# USBHeaders.net
KiCad netlist of a schematic drawn in Altium Designer
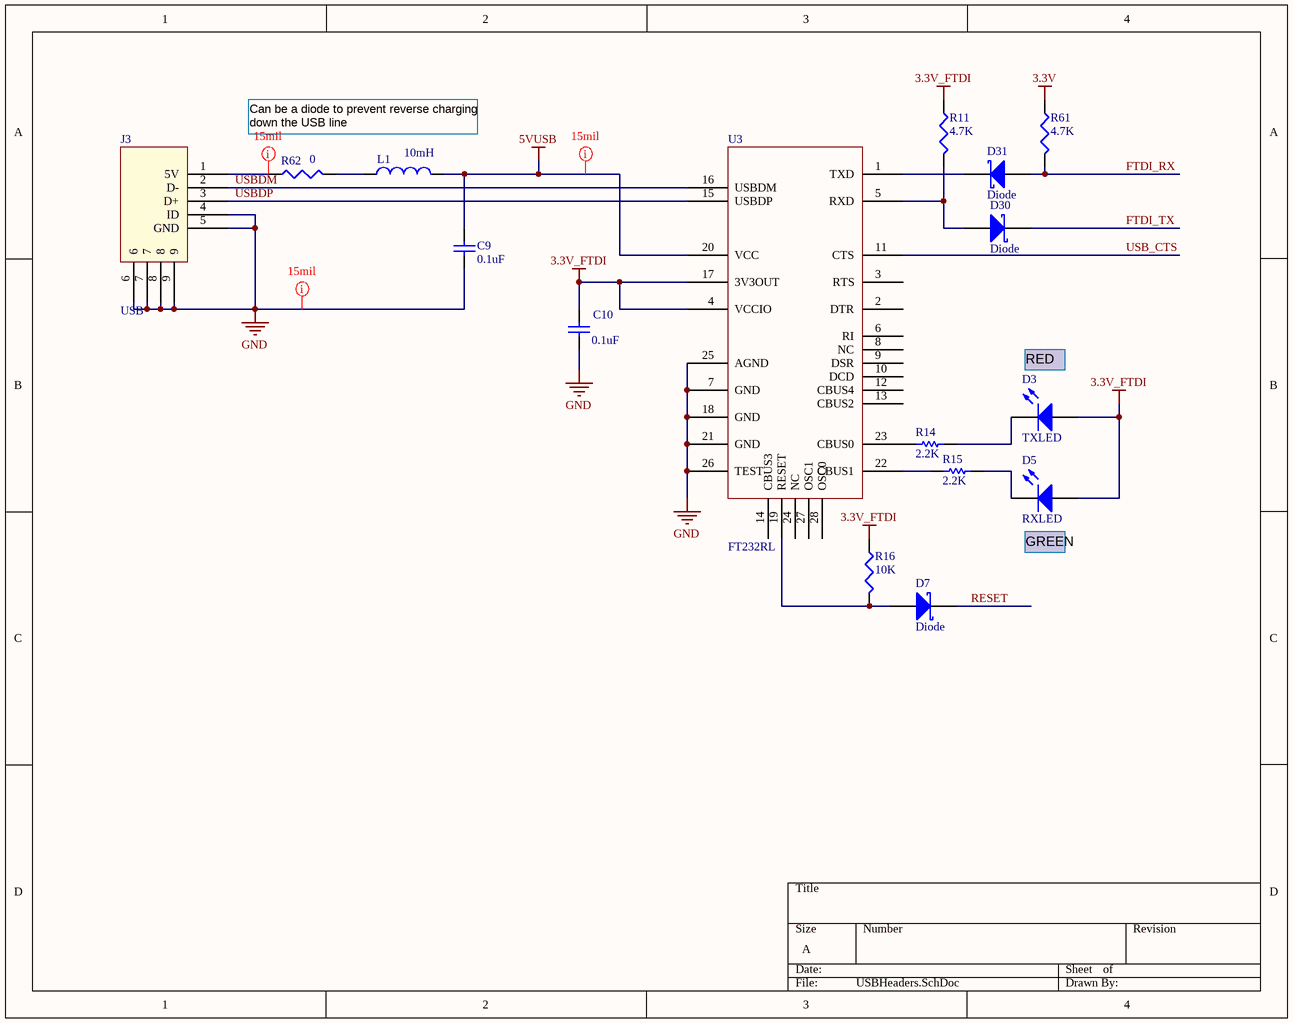
[diagram p0: USBHeaders.SchDoc]

(export (version "E")
  (design (tool "Eeschema 10.0.6"))
  (components
    (comp (ref "C9")
      (value "0.1uF")
      (footprint "CAPC1005L")
      (description "Capacitor")
      (fields (field (name "PUBLISHER") "Altium Limited"))
      (libsource (lib "Miscellaneous Devices") (part "Cap"))
    )
    (comp (ref "C10")
      (value "0.1uF")
      (footprint "CAPC1005L")
      (description "Capacitor")
      (fields (field (name "PUBLISHER") "Altium Limited"))
      (libsource (lib "Miscellaneous Devices") (part "Cap"))
    )
    (comp (ref "D3")
      (value "TXLED")
      (footprint "SurfaceMount(603)")
      (description "Typical RED, GREEN, YELLOW, AMBER GaAs LED")
      (fields (field (name "PUBLISHER") "Altium Limited"))
      (libsource (lib "Miscellaneous Devices") (part "LED2"))
    )
    (comp (ref "D5")
      (value "RXLED")
      (footprint "SurfaceMount(603)")
      (description "Typical RED, GREEN, YELLOW, AMBER GaAs LED")
      (fields (field (name "PUBLISHER") "Altium Limited"))
      (libsource (lib "Miscellaneous Devices") (part "LED2"))
    )
    (comp (ref "D7")
      (value "Diode")
      (footprint "SurfaceMount(603)")
      (libsource (lib "mrone") (part "SchottkeyDiode"))
    )
    (comp (ref "D30")
      (value "Diode")
      (footprint "SurfaceMount(603)")
      (libsource (lib "mrone") (part "SchottkeyDiode"))
    )
    (comp (ref "D31")
      (value "Diode")
      (footprint "SurfaceMount(603)")
      (libsource (lib "mrone") (part "SchottkeyDiode"))
    )
    (comp (ref "J3")
      (value "USB")
      (footprint "USB Minib (thru-hole)")
      (libsource (lib "mrone") (part "USB-ConnTH"))
    )
    (comp (ref "L1")
      (value "10mH")
      (footprint "INDC2012L")
      (description "Inductor")
      (fields (field (name "PUBLISHER") "Altium Limited"))
      (libsource (lib "Miscellaneous Devices") (part "Inductor"))
    )
    (comp (ref "R11")
      (value "4.7K")
      (footprint "RESC1608L")
      (description "Resistor")
      (fields (field (name "Comment") "Res3") (field (name "PUBLISHER") "Altium Limited"))
      (libsource (lib "Miscellaneous Devices") (part "Res3"))
    )
    (comp (ref "R14")
      (value "2.2K")
      (footprint "RESC1608L")
      (description "Resistor")
      (fields (field (name "PUBLISHER") "Altium Limited"))
      (libsource (lib "Miscellaneous Devices") (part "Res1"))
    )
    (comp (ref "R15")
      (value "2.2K")
      (footprint "RESC1608L")
      (description "Resistor")
      (fields (field (name "PUBLISHER") "Altium Limited"))
      (libsource (lib "Miscellaneous Devices") (part "Res1"))
    )
    (comp (ref "R16")
      (value "10K")
      (footprint "RESC1608L")
      (description "Resistor")
      (fields (field (name "Comment") "Res3") (field (name "PUBLISHER") "Altium Limited"))
      (libsource (lib "Miscellaneous Devices") (part "Res3"))
    )
    (comp (ref "R61")
      (value "4.7K")
      (footprint "RESC1608L")
      (description "Resistor")
      (fields (field (name "Comment") "Res3") (field (name "PUBLISHER") "Altium Limited"))
      (libsource (lib "Miscellaneous Devices") (part "Res3"))
    )
    (comp (ref "R62")
      (value "0")
      (footprint "RESC1608L")
      (description "Resistor")
      (fields (field (name "Comment") "Res3") (field (name "PUBLISHER") "Altium Limited"))
      (libsource (lib "Miscellaneous Devices") (part "Res3"))
    )
    (comp (ref "U3") (value "FT232RL") (footprint "SSOP-28") (libsource (lib "mrone") (part "FT232RL")))
  )
  (nets
    (net (code "1") (name "/FTDI_RX") (class "Default")
      (node (ref "D31") (pin "2") (pinfunction "A_2") (pintype "passive"))
      (node (ref "R61") (pin "2") (pinfunction "2_2") (pintype "passive"))
    )
    (net (code "2") (name "/FTDI_TX") (class "Default")
      (node (ref "D30") (pin "1") (pinfunction "K_1") (pintype "passive"))
    )
    (net (code "3") (name "/RESET") (class "Default")
      (node (ref "D7") (pin "1") (pinfunction "K_1") (pintype "passive"))
    )
    (net (code "4") (name "/USBDM") (class "Default")
      (node (ref "J3") (pin "2") (pinfunction "D-_2") (pintype "passive"))
      (node (ref "U3") (pin "16") (pinfunction "USBDM_16") (pintype "passive"))
    )
    (net (code "5") (name "/USBDP") (class "Default")
      (node (ref "J3") (pin "3") (pinfunction "D+_3") (pintype "passive"))
      (node (ref "U3") (pin "15") (pinfunction "USBDP_15") (pintype "passive"))
    )
    (net (code "6") (name "/USB_CTS") (class "Default")
      (node (ref "U3") (pin "11") (pinfunction "CTS_11") (pintype "passive"))
    )
    (net (code "7") (name "3.3V") (class "Default")
      (node (ref "R61") (pin "1") (pinfunction "1_1") (pintype "passive"))
    )
    (net (code "8") (name "3.3V_FTDI") (class "Default")
      (node (ref "C10") (pin "2") (pinfunction "2_2") (pintype "passive"))
      (node (ref "D3") (pin "1") (pinfunction "A_1") (pintype "passive"))
      (node (ref "D5") (pin "1") (pinfunction "A_1") (pintype "passive"))
      (node (ref "R11") (pin "1") (pinfunction "1_1") (pintype "passive"))
      (node (ref "R16") (pin "1") (pinfunction "1_1") (pintype "passive"))
      (node (ref "U3") (pin "17") (pinfunction "3V3OUT_17") (pintype "passive"))
      (node (ref "U3") (pin "4") (pinfunction "VCCIO_4") (pintype "passive"))
    )
    (net (code "9") (name "5VUSB") (class "Default")
      (node (ref "C9") (pin "2") (pinfunction "2_2") (pintype "passive"))
      (node (ref "L1") (pin "2") (pinfunction "2_2") (pintype "passive"))
      (node (ref "U3") (pin "20") (pinfunction "VCC_20") (pintype "passive"))
    )
    (net (code "10") (name "GND") (class "Default")
      (node (ref "C10") (pin "1") (pinfunction "1_1") (pintype "passive"))
      (node (ref "C9") (pin "1") (pinfunction "1_1") (pintype "passive"))
      (node (ref "J3") (pin "4") (pinfunction "ID_4") (pintype "passive"))
      (node (ref "J3") (pin "5") (pinfunction "GND_5") (pintype "passive"))
      (node (ref "J3") (pin "6") (pinfunction "6_6") (pintype "passive"))
      (node (ref "J3") (pin "7") (pinfunction "7_7") (pintype "passive"))
      (node (ref "J3") (pin "8") (pinfunction "8_8") (pintype "passive"))
      (node (ref "J3") (pin "9") (pinfunction "9_9") (pintype "passive"))
      (node (ref "U3") (pin "18") (pinfunction "GND_18") (pintype "passive"))
      (node (ref "U3") (pin "21") (pinfunction "GND_21") (pintype "passive"))
      (node (ref "U3") (pin "25") (pinfunction "AGND_25") (pintype "passive"))
      (node (ref "U3") (pin "26") (pinfunction "TEST_26") (pintype "passive"))
      (node (ref "U3") (pin "7") (pinfunction "GND_7") (pintype "passive"))
    )
    (net (code "11") (name "Net-(D3-K)") (class "Default")
      (node (ref "D3") (pin "2") (pinfunction "K_2") (pintype "passive"))
      (node (ref "R14") (pin "2") (pinfunction "2_2") (pintype "passive"))
    )
    (net (code "12") (name "Net-(D5-K)") (class "Default")
      (node (ref "D5") (pin "2") (pinfunction "K_2") (pintype "passive"))
      (node (ref "R15") (pin "2") (pinfunction "2_2") (pintype "passive"))
    )
    (net (code "13") (name "Net-(D7-A)") (class "Default")
      (node (ref "D7") (pin "2") (pinfunction "A_2") (pintype "passive"))
      (node (ref "R16") (pin "2") (pinfunction "2_2") (pintype "passive"))
      (node (ref "U3") (pin "19") (pinfunction "RESET_19") (pintype "passive"))
    )
    (net (code "14") (name "Net-(D30-A)") (class "Default")
      (node (ref "D30") (pin "2") (pinfunction "A_2") (pintype "passive"))
      (node (ref "R11") (pin "2") (pinfunction "2_2") (pintype "passive"))
      (node (ref "U3") (pin "5") (pinfunction "RXD_5") (pintype "passive"))
    )
    (net (code "15") (name "Net-(D31-K)") (class "Default")
      (node (ref "D31") (pin "1") (pinfunction "K_1") (pintype "passive"))
      (node (ref "U3") (pin "1") (pinfunction "TXD_1") (pintype "passive"))
    )
    (net (code "16") (name "Net-(J3-5V)") (class "Default")
      (node (ref "J3") (pin "1") (pinfunction "5V_1") (pintype "passive"))
      (node (ref "R62") (pin "1") (pinfunction "1_1") (pintype "passive"))
    )
    (net (code "17") (name "Net-(L1-Pad1)") (class "Default")
      (node (ref "L1") (pin "1") (pinfunction "1_1") (pintype "passive"))
      (node (ref "R62") (pin "2") (pinfunction "2_2") (pintype "passive"))
    )
    (net (code "18") (name "Net-(U3-CBUS0)") (class "Default")
      (node (ref "R14") (pin "1") (pinfunction "1_1") (pintype "passive"))
      (node (ref "U3") (pin "23") (pinfunction "CBUS0_23") (pintype "passive"))
    )
    (net (code "19") (name "Net-(U3-CBUS1)") (class "Default")
      (node (ref "R15") (pin "1") (pinfunction "1_1") (pintype "passive"))
      (node (ref "U3") (pin "22") (pinfunction "CBUS1_22") (pintype "passive"))
    )
    (net (code "20") (name "unconnected-(U3-CBUS2-Pad13)") (class "Default")
      (node (ref "U3") (pin "13") (pinfunction "CBUS2_13") (pintype "passive"))
    )
    (net (code "21") (name "unconnected-(U3-CBUS3-Pad14)") (class "Default")
      (node (ref "U3") (pin "14") (pinfunction "CBUS3_14") (pintype "passive"))
    )
    (net (code "22") (name "unconnected-(U3-CBUS4-Pad12)") (class "Default")
      (node (ref "U3") (pin "12") (pinfunction "CBUS4_12") (pintype "passive"))
    )
    (net (code "23") (name "unconnected-(U3-DCD-Pad10)") (class "Default")
      (node (ref "U3") (pin "10") (pinfunction "DCD_10") (pintype "passive"))
    )
    (net (code "24") (name "unconnected-(U3-DSR-Pad9)") (class "Default")
      (node (ref "U3") (pin "9") (pinfunction "DSR_9") (pintype "passive"))
    )
    (net (code "25") (name "unconnected-(U3-DTR-Pad2)") (class "Default")
      (node (ref "U3") (pin "2") (pinfunction "DTR_2") (pintype "passive"))
    )
    (net (code "26") (name "unconnected-(U3-NC-Pad8)") (class "Default")
      (node (ref "U3") (pin "8") (pinfunction "NC_8") (pintype "passive"))
    )
    (net (code "27") (name "unconnected-(U3-NC-Pad24)") (class "Default")
      (node (ref "U3") (pin "24") (pinfunction "NC_24") (pintype "passive"))
    )
    (net (code "28") (name "unconnected-(U3-OSC0-Pad28)") (class "Default")
      (node (ref "U3") (pin "28") (pinfunction "OSC0_28") (pintype "passive"))
    )
    (net (code "29") (name "unconnected-(U3-OSC1-Pad27)") (class "Default")
      (node (ref "U3") (pin "27") (pinfunction "OSC1_27") (pintype "passive"))
    )
    (net (code "30") (name "unconnected-(U3-RI-Pad6)") (class "Default")
      (node (ref "U3") (pin "6") (pinfunction "RI_6") (pintype "passive"))
    )
    (net (code "31") (name "unconnected-(U3-RTS-Pad3)") (class "Default")
      (node (ref "U3") (pin "3") (pinfunction "RTS_3") (pintype "passive"))
    )
  )
)
